# Autopilot_remote_receiver.net
KiCad netlist of a schematic drawn in EAGLE
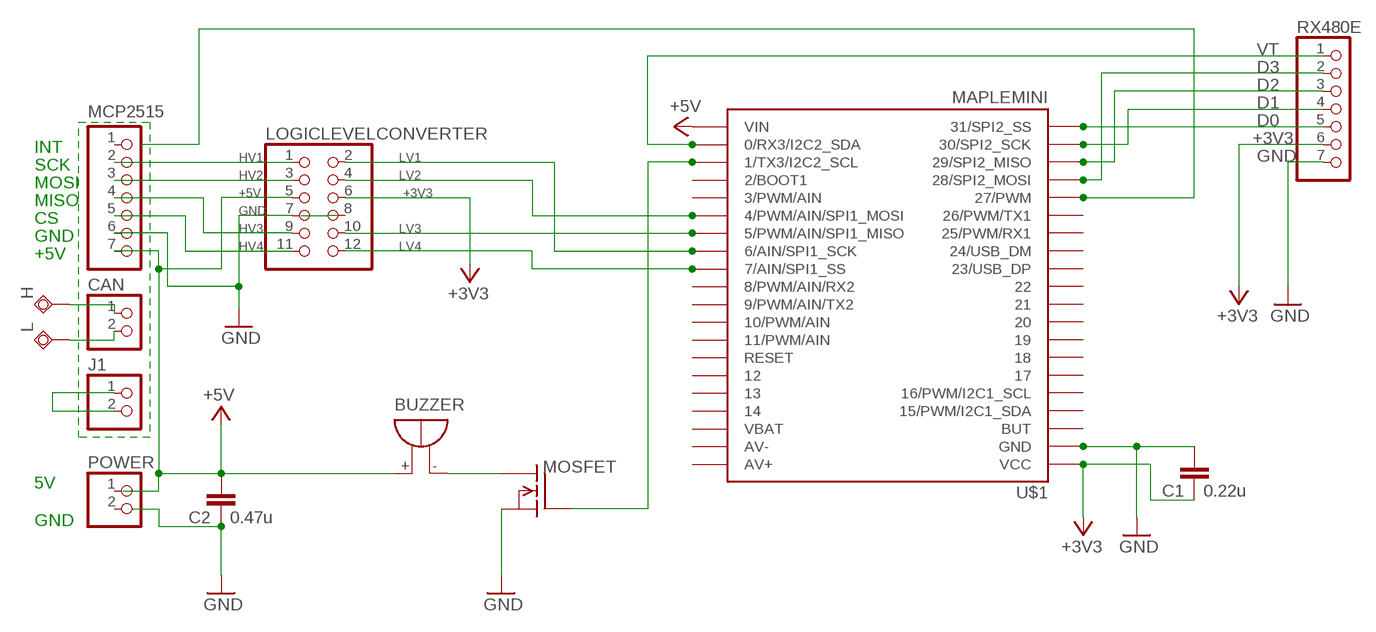
[diagram p0: schematic, sheet 1]

(export (version "E")
  (design (tool "Eeschema 10.0.6"))
  (components
    (comp (ref "BUZZER")
      (value "F/BC35")
      (footprint "eagle-import:F_BC35")
      (libsource (lib "eagle-import") (part "F/BC35"))
    )
    (comp (ref "C1")
      (value "0.22u")
      (footprint "eagle-import:C050-025X075")
      (libsource (lib "eagle-import") (part "C-EU050-025X075"))
    )
    (comp (ref "C2")
      (value "0.47u")
      (footprint "eagle-import:C050-025X075")
      (libsource (lib "eagle-import") (part "C-EU050-025X075"))
    )
    (comp (ref "CAN")
      (value "PINHD-1X2")
      (footprint "eagle-import:1X02")
      (libsource (lib "eagle-import") (part "PINHD-1X2"))
    )
    (comp (ref "H")
      (value "TPSQPAD1-20")
      (footprint "eagle-import:P1-20")
      (libsource (lib "eagle-import") (part "TPSQPAD1-20"))
    )
    (comp (ref "J1")
      (value "PINHD-1X2")
      (footprint "eagle-import:1X02")
      (libsource (lib "eagle-import") (part "PINHD-1X2"))
    )
    (comp (ref "L")
      (value "TPSQPAD1-20")
      (footprint "eagle-import:P1-20")
      (libsource (lib "eagle-import") (part "TPSQPAD1-20"))
    )
    (comp (ref "LOGICLEVELCONVERTER")
      (value "PINHD-2X6")
      (footprint "eagle-import:2X06")
      (libsource (lib "eagle-import") (part "PINHD-2X6"))
    )
    (comp (ref "MCP2515")
      (value "PINHD-1X7")
      (footprint "eagle-import:1X07")
      (libsource (lib "eagle-import") (part "PINHD-1X7"))
    )
    (comp (ref "MOSFET")
      (value "BUZ11")
      (footprint "eagle-import:TO220")
      (libsource (lib "eagle-import") (part "BUZ11"))
    )
    (comp (ref "POWER")
      (value "PINHD-1X2")
      (footprint "eagle-import:1X02")
      (libsource (lib "eagle-import") (part "PINHD-1X2"))
    )
    (comp (ref "RX480E")
      (value "PINHD-1X7")
      (footprint "eagle-import:1X07")
      (libsource (lib "eagle-import") (part "PINHD-1X7"))
    )
    (comp (ref "U$1")
      (value "MAPLEMINI")
      (footprint "eagle-import:20-DIP")
      (libsource (lib "eagle-import") (part "MAPLEMINI"))
    )
  )
  (nets
    (net (code "1") (name "+3V3") (class "Default")
      (node (ref "C1") (pin "1") (pinfunction "1_1") (pintype "passive"))
      (node (ref "LOGICLEVELCONVERTER") (pin "6") (pinfunction "6_6") (pintype "passive"))
      (node (ref "RX480E") (pin "6") (pinfunction "6_6") (pintype "passive"))
      (node (ref "U$1") (pin "1") (pinfunction "VCC_1") (pintype "bidirectional"))
    )
    (net (code "2") (name "+5V") (class "Default")
      (node (ref "BUZZER") (pin "+") (pinfunction "+_+") (pintype "passive"))
      (node (ref "C2") (pin "2") (pinfunction "2_2") (pintype "passive"))
      (node (ref "LOGICLEVELCONVERTER") (pin "5") (pinfunction "5_5") (pintype "passive"))
      (node (ref "MCP2515") (pin "7") (pinfunction "7_7") (pintype "passive"))
      (node (ref "U$1") (pin "21") (pinfunction "VIN_21") (pintype "bidirectional"))
    )
    (net (code "3") (name "/D0") (class "Default")
      (node (ref "RX480E") (pin "5") (pinfunction "5_5") (pintype "passive"))
      (node (ref "U$1") (pin "20") (pinfunction "31/SPI2_SS_20") (pintype "bidirectional"))
    )
    (net (code "4") (name "/D1") (class "Default")
      (node (ref "RX480E") (pin "4") (pinfunction "4_4") (pintype "passive"))
      (node (ref "U$1") (pin "19") (pinfunction "30/SPI2_SCK_19") (pintype "bidirectional"))
    )
    (net (code "5") (name "/D2") (class "Default")
      (node (ref "RX480E") (pin "3") (pinfunction "3_3") (pintype "passive"))
      (node (ref "U$1") (pin "18") (pinfunction "29/SPI2_MISO_18") (pintype "bidirectional"))
    )
    (net (code "6") (name "/D3") (class "Default")
      (node (ref "RX480E") (pin "2") (pinfunction "2_2") (pintype "passive"))
      (node (ref "U$1") (pin "17") (pinfunction "28/SPI2_MOSI_17") (pintype "bidirectional"))
    )
    (net (code "7") (name "/HV1") (class "Default")
      (node (ref "LOGICLEVELCONVERTER") (pin "1") (pinfunction "1_1") (pintype "passive"))
      (node (ref "MCP2515") (pin "2") (pinfunction "2_2") (pintype "passive"))
    )
    (net (code "8") (name "/HV2") (class "Default")
      (node (ref "LOGICLEVELCONVERTER") (pin "3") (pinfunction "3_3") (pintype "passive"))
      (node (ref "MCP2515") (pin "3") (pinfunction "3_3") (pintype "passive"))
    )
    (net (code "9") (name "/HV3") (class "Default")
      (node (ref "LOGICLEVELCONVERTER") (pin "9") (pinfunction "9_9") (pintype "passive"))
      (node (ref "MCP2515") (pin "4") (pinfunction "4_4") (pintype "passive"))
    )
    (net (code "10") (name "/HV4") (class "Default")
      (node (ref "LOGICLEVELCONVERTER") (pin "11") (pinfunction "11_11") (pintype "passive"))
      (node (ref "MCP2515") (pin "5") (pinfunction "5_5") (pintype "passive"))
    )
    (net (code "11") (name "/LV1") (class "Default")
      (node (ref "LOGICLEVELCONVERTER") (pin "2") (pinfunction "2_2") (pintype "passive"))
      (node (ref "U$1") (pin "28") (pinfunction "6/AIN/SPI1_SCK_28") (pintype "bidirectional"))
    )
    (net (code "12") (name "/LV2") (class "Default")
      (node (ref "LOGICLEVELCONVERTER") (pin "4") (pinfunction "4_4") (pintype "passive"))
      (node (ref "U$1") (pin "26") (pinfunction "4/PWM/AIN/SPI1_MOSI_26") (pintype "bidirectional"))
    )
    (net (code "13") (name "/LV3") (class "Default")
      (node (ref "LOGICLEVELCONVERTER") (pin "10") (pinfunction "10_10") (pintype "passive"))
      (node (ref "U$1") (pin "27") (pinfunction "5/PWM/AIN/SPI1_MISO_27") (pintype "bidirectional"))
    )
    (net (code "14") (name "/LV4") (class "Default")
      (node (ref "LOGICLEVELCONVERTER") (pin "12") (pinfunction "12_12") (pintype "passive"))
      (node (ref "U$1") (pin "29") (pinfunction "7/AIN/SPI1_SS_29") (pintype "bidirectional"))
    )
    (net (code "15") (name "/VT") (class "Default")
      (node (ref "RX480E") (pin "1") (pinfunction "1_1") (pintype "passive"))
      (node (ref "U$1") (pin "22") (pinfunction "0/RX3/I2C2_SDA_22") (pintype "bidirectional"))
    )
    (net (code "16") (name "GND") (class "Default")
      (node (ref "C1") (pin "2") (pinfunction "2_2") (pintype "passive"))
      (node (ref "C2") (pin "1") (pinfunction "1_1") (pintype "passive"))
      (node (ref "LOGICLEVELCONVERTER") (pin "7") (pinfunction "7_7") (pintype "passive"))
      (node (ref "MCP2515") (pin "6") (pinfunction "6_6") (pintype "passive"))
      (node (ref "MOSFET") (pin "3") (pinfunction "S_3") (pintype "passive"))
      (node (ref "RX480E") (pin "7") (pinfunction "7_7") (pintype "passive"))
      (node (ref "U$1") (pin "2") (pinfunction "GND_2") (pintype "bidirectional"))
    )
    (net (code "17") (name "Net-(CAN-Pad1)") (class "Default")
      (node (ref "CAN") (pin "1") (pinfunction "1_1") (pintype "passive"))
      (node (ref "H") (pin "TP") (pinfunction "TP_TP") (pintype "input"))
    )
    (net (code "18") (name "Net-(CAN-Pad2)") (class "Default")
      (node (ref "CAN") (pin "2") (pinfunction "2_2") (pintype "passive"))
      (node (ref "L") (pin "TP") (pinfunction "TP_TP") (pintype "input"))
    )
    (net (code "19") (name "Net-(J1-Pad1)") (class "Default")
      (node (ref "J1") (pin "1") (pinfunction "1_1") (pintype "passive"))
      (node (ref "J1") (pin "2") (pinfunction "2_2") (pintype "passive"))
    )
    (net (code "20") (name "Net-(MOSFET-D)") (class "Default")
      (node (ref "BUZZER") (pin "-") (pinfunction "-_-") (pintype "passive"))
      (node (ref "MOSFET") (pin "2") (pinfunction "D_2") (pintype "passive"))
    )
    (net (code "21") (name "Net-(MOSFET-G)") (class "Default")
      (node (ref "MOSFET") (pin "1") (pinfunction "G_1") (pintype "passive"))
      (node (ref "U$1") (pin "23") (pinfunction "1/TX3/I2C2_SCL_23") (pintype "bidirectional"))
    )
    (net (code "22") (name "unconnected-(LOGICLEVELCONVERTER-Pad8)") (class "Default")
      (node (ref "LOGICLEVELCONVERTER") (pin "8") (pinfunction "8_8") (pintype "passive"))
    )
    (net (code "23") (name "unconnected-(MCP2515-Pad1)") (class "Default")
      (node (ref "MCP2515") (pin "1") (pinfunction "1_1") (pintype "passive"))
    )
    (net (code "24") (name "unconnected-(POWER-Pad1)") (class "Default")
      (node (ref "POWER") (pin "1") (pinfunction "1_1") (pintype "passive"))
    )
    (net (code "25") (name "unconnected-(POWER-Pad2)") (class "Default")
      (node (ref "POWER") (pin "2") (pinfunction "2_2") (pintype "passive"))
    )
    (net (code "26") (name "unconnected-(U$1-2{slash}BOOT1-Pad24)") (class "Default")
      (node (ref "U$1") (pin "24") (pinfunction "2/BOOT1_24") (pintype "bidirectional"))
    )
    (net (code "27") (name "unconnected-(U$1-3{slash}PWM{slash}AIN-Pad25)") (class "Default")
      (node (ref "U$1") (pin "25") (pinfunction "3/PWM/AIN_25") (pintype "bidirectional"))
    )
    (net (code "28") (name "unconnected-(U$1-8{slash}PWM{slash}AIN{slash}RX2-Pad30)") (class "Default")
      (node (ref "U$1") (pin "30") (pinfunction "8/PWM/AIN/RX2_30") (pintype "bidirectional"))
    )
    (net (code "29") (name "unconnected-(U$1-9{slash}PWM{slash}AIN{slash}TX2-Pad31)") (class "Default")
      (node (ref "U$1") (pin "31") (pinfunction "9/PWM/AIN/TX2_31") (pintype "bidirectional"))
    )
    (net (code "30") (name "unconnected-(U$1-10{slash}PWM{slash}AIN-Pad32)") (class "Default")
      (node (ref "U$1") (pin "32") (pinfunction "10/PWM/AIN_32") (pintype "bidirectional"))
    )
    (net (code "31") (name "unconnected-(U$1-11{slash}PWM{slash}AIN-Pad33)") (class "Default")
      (node (ref "U$1") (pin "33") (pinfunction "11/PWM/AIN_33") (pintype "bidirectional"))
    )
    (net (code "32") (name "unconnected-(U$1-12-Pad35)") (class "Default")
      (node (ref "U$1") (pin "35") (pinfunction "12_35") (pintype "bidirectional"))
    )
    (net (code "33") (name "unconnected-(U$1-13-Pad36)") (class "Default")
      (node (ref "U$1") (pin "36") (pinfunction "13_36") (pintype "bidirectional"))
    )
    (net (code "34") (name "unconnected-(U$1-14-Pad37)") (class "Default")
      (node (ref "U$1") (pin "37") (pinfunction "14_37") (pintype "bidirectional"))
    )
    (net (code "35") (name "unconnected-(U$1-15{slash}PWM{slash}I2C1_SDA-Pad4)") (class "Default")
      (node (ref "U$1") (pin "4") (pinfunction "15/PWM/I2C1_SDA_4") (pintype "bidirectional"))
    )
    (net (code "36") (name "unconnected-(U$1-16{slash}PWM{slash}I2C1_SCL-Pad5)") (class "Default")
      (node (ref "U$1") (pin "5") (pinfunction "16/PWM/I2C1_SCL_5") (pintype "bidirectional"))
    )
    (net (code "37") (name "unconnected-(U$1-17-Pad6)") (class "Default")
      (node (ref "U$1") (pin "6") (pinfunction "17_6") (pintype "bidirectional"))
    )
    (net (code "38") (name "unconnected-(U$1-18-Pad7)") (class "Default")
      (node (ref "U$1") (pin "7") (pinfunction "18_7") (pintype "bidirectional"))
    )
    (net (code "39") (name "unconnected-(U$1-19-Pad8)") (class "Default")
      (node (ref "U$1") (pin "8") (pinfunction "19_8") (pintype "bidirectional"))
    )
    (net (code "40") (name "unconnected-(U$1-20-Pad9)") (class "Default")
      (node (ref "U$1") (pin "9") (pinfunction "20_9") (pintype "bidirectional"))
    )
    (net (code "41") (name "unconnected-(U$1-21-Pad10)") (class "Default")
      (node (ref "U$1") (pin "10") (pinfunction "21_10") (pintype "bidirectional"))
    )
    (net (code "42") (name "unconnected-(U$1-22-Pad11)") (class "Default")
      (node (ref "U$1") (pin "11") (pinfunction "22_11") (pintype "bidirectional"))
    )
    (net (code "43") (name "unconnected-(U$1-23{slash}USB_DP-Pad12)") (class "Default")
      (node (ref "U$1") (pin "12") (pinfunction "23/USB_DP_12") (pintype "bidirectional"))
    )
    (net (code "44") (name "unconnected-(U$1-24{slash}USB_DM-Pad13)") (class "Default")
      (node (ref "U$1") (pin "13") (pinfunction "24/USB_DM_13") (pintype "bidirectional"))
    )
    (net (code "45") (name "unconnected-(U$1-25{slash}PWM{slash}RX1-Pad14)") (class "Default")
      (node (ref "U$1") (pin "14") (pinfunction "25/PWM/RX1_14") (pintype "bidirectional"))
    )
    (net (code "46") (name "unconnected-(U$1-26{slash}PWM{slash}TX1-Pad15)") (class "Default")
      (node (ref "U$1") (pin "15") (pinfunction "26/PWM/TX1_15") (pintype "bidirectional"))
    )
    (net (code "47") (name "unconnected-(U$1-27{slash}PWM-Pad16)") (class "Default")
      (node (ref "U$1") (pin "16") (pinfunction "27/PWM_16") (pintype "bidirectional"))
    )
    (net (code "48") (name "unconnected-(U$1-AV+-Pad40)") (class "Default")
      (node (ref "U$1") (pin "40") (pinfunction "AV+_40") (pintype "bidirectional"))
    )
    (net (code "49") (name "unconnected-(U$1-AV--Pad39)") (class "Default")
      (node (ref "U$1") (pin "39") (pinfunction "AV-_39") (pintype "bidirectional"))
    )
    (net (code "50") (name "unconnected-(U$1-BUT-Pad3)") (class "Default")
      (node (ref "U$1") (pin "3") (pinfunction "BUT_3") (pintype "bidirectional"))
    )
    (net (code "51") (name "unconnected-(U$1-RESET-Pad34)") (class "Default")
      (node (ref "U$1") (pin "34") (pinfunction "RESET_34") (pintype "bidirectional"))
    )
    (net (code "52") (name "unconnected-(U$1-VBAT-Pad38)") (class "Default")
      (node (ref "U$1") (pin "38") (pinfunction "VBAT_38") (pintype "bidirectional"))
    )
  )
)
